# a401-diode-distortion.net
KiCad netlist of a schematic drawn in EAGLE
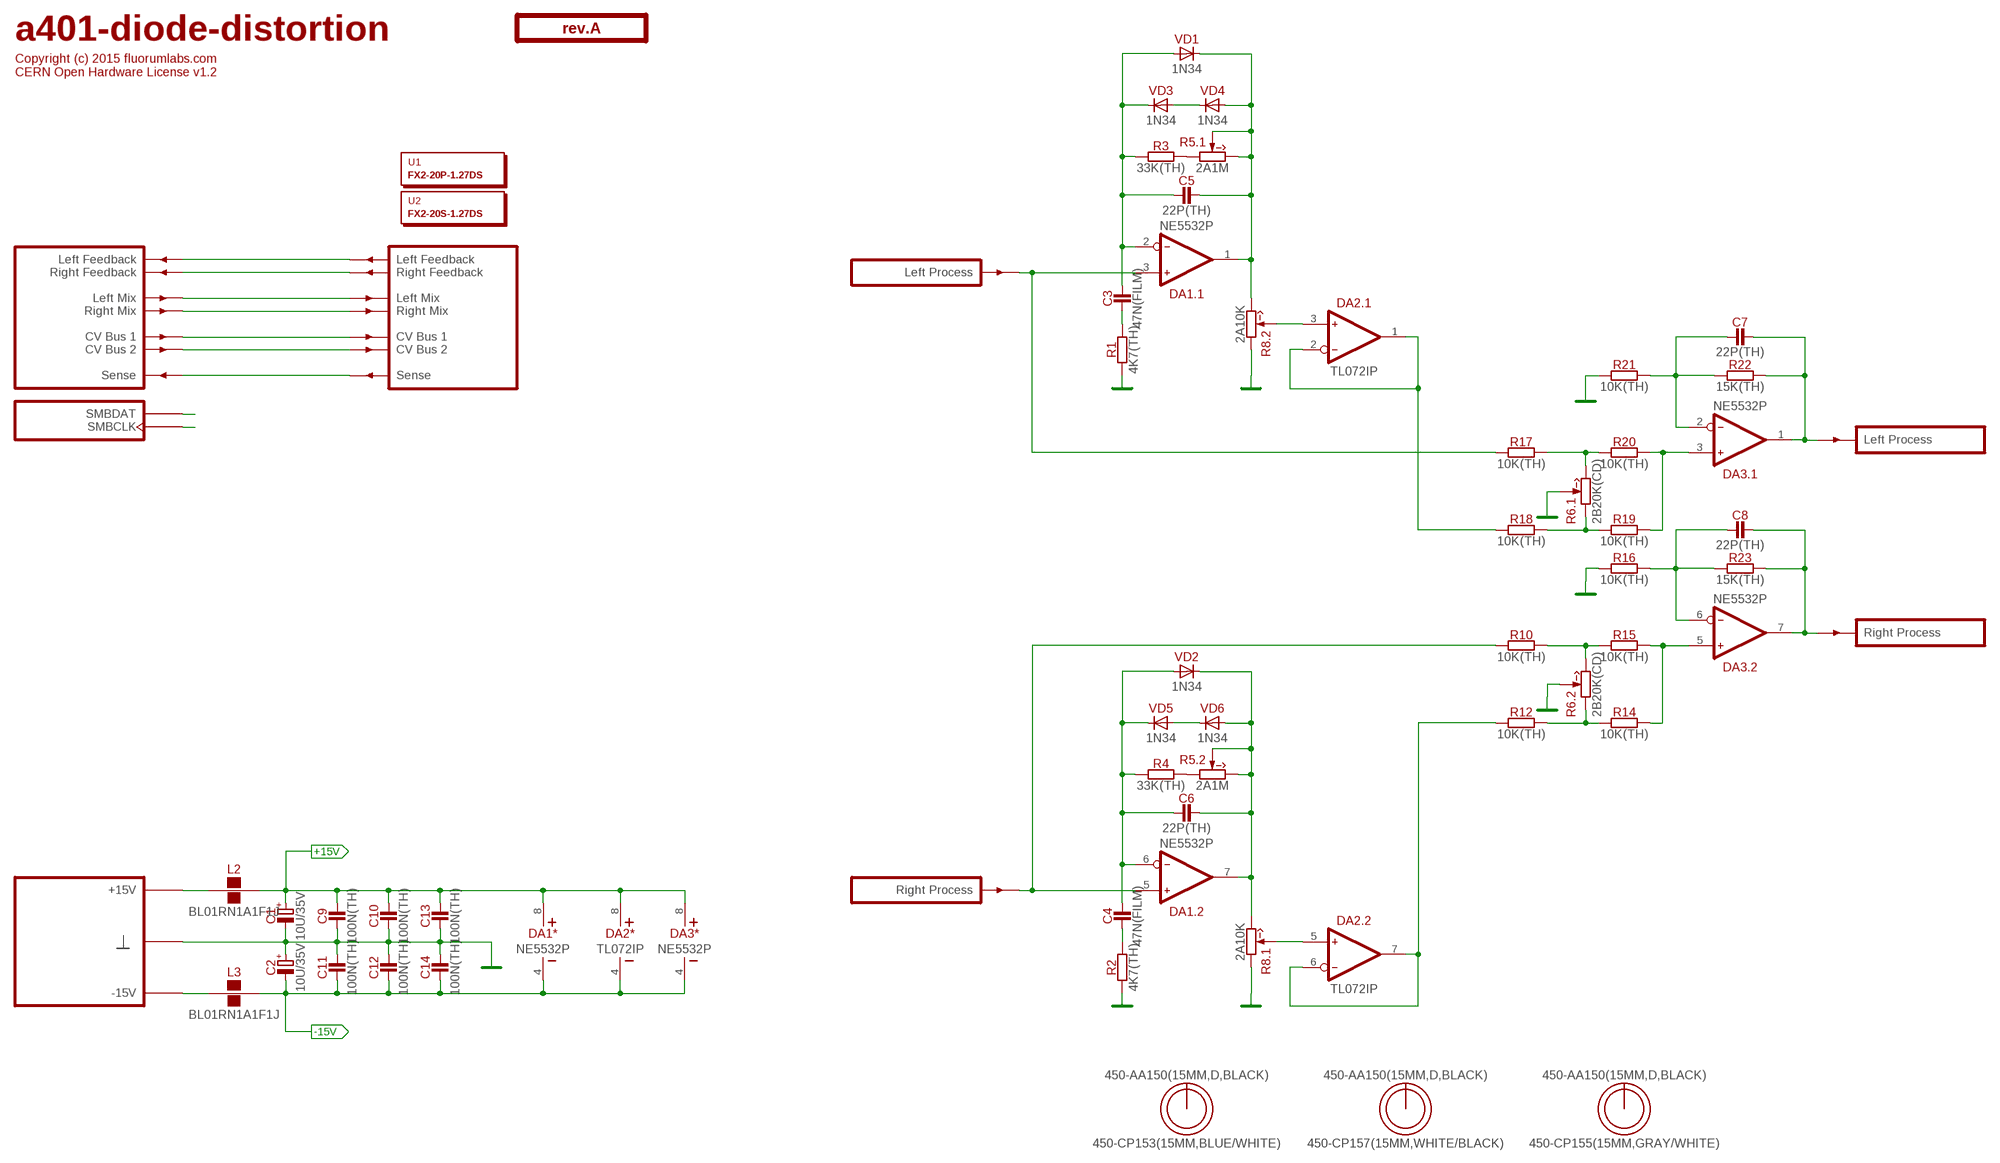
[diagram p0: schematic, sheet 1]

(export (version "E")
  (design (tool "Eeschema 10.0.6"))
  (components
    (comp (ref "C1")
      (value "10U/35V")
      (footprint "eagle-import:E2-5")
      (libsource (lib "eagle-import") (part "?10U/35V"))
    )
    (comp (ref "C2")
      (value "10U/35V")
      (footprint "eagle-import:E2-5")
      (libsource (lib "eagle-import") (part "?10U/35V"))
    )
    (comp (ref "C3")
      (value "47N(FILM)")
      (footprint "eagle-import:C050-025X075")
      (libsource (lib "eagle-import") (part "?47N(FILM)"))
    )
    (comp (ref "C4")
      (value "47N(FILM)")
      (footprint "eagle-import:C050-025X075")
      (libsource (lib "eagle-import") (part "?47N(FILM)"))
    )
    (comp (ref "C5")
      (value "22P(TH)")
      (footprint "eagle-import:C050-024X044")
      (libsource (lib "eagle-import") (part "?22P(TH)"))
    )
    (comp (ref "C6")
      (value "22P(TH)")
      (footprint "eagle-import:C050-024X044")
      (libsource (lib "eagle-import") (part "?22P(TH)"))
    )
    (comp (ref "C7")
      (value "22P(TH)")
      (footprint "eagle-import:C050-024X044")
      (libsource (lib "eagle-import") (part "?22P(TH)"))
    )
    (comp (ref "C8")
      (value "22P(TH)")
      (footprint "eagle-import:C050-024X044")
      (libsource (lib "eagle-import") (part "?22P(TH)"))
    )
    (comp (ref "C9")
      (value "100N(TH)")
      (footprint "eagle-import:C050-024X044")
      (libsource (lib "eagle-import") (part "?100N(TH)"))
    )
    (comp (ref "C10")
      (value "100N(TH)")
      (footprint "eagle-import:C050-024X044")
      (libsource (lib "eagle-import") (part "?100N(TH)"))
    )
    (comp (ref "C11")
      (value "100N(TH)")
      (footprint "eagle-import:C050-024X044")
      (libsource (lib "eagle-import") (part "?100N(TH)"))
    )
    (comp (ref "C12")
      (value "100N(TH)")
      (footprint "eagle-import:C050-024X044")
      (libsource (lib "eagle-import") (part "?100N(TH)"))
    )
    (comp (ref "C13")
      (value "100N(TH)")
      (footprint "eagle-import:C050-024X044")
      (libsource (lib "eagle-import") (part "?100N(TH)"))
    )
    (comp (ref "C14")
      (value "100N(TH)")
      (footprint "eagle-import:C050-024X044")
      (libsource (lib "eagle-import") (part "?100N(TH)"))
    )
    (comp (ref "DA1")
      (value "NE5532P")
      (footprint "eagle-import:DIP-8")
      (libsource (lib "eagle-import") (part "NE5532P"))
    )
    (comp (ref "DA2")
      (value "TL072IP")
      (footprint "eagle-import:DIP-8")
      (libsource (lib "eagle-import") (part "TL072IP"))
    )
    (comp (ref "DA3")
      (value "NE5532P")
      (footprint "eagle-import:DIP-8")
      (libsource (lib "eagle-import") (part "NE5532P"))
    )
    (comp (ref "L2")
      (value "BL01RN1A1F1J")
      (footprint "eagle-import:BL01RN1A")
      (libsource (lib "eagle-import") (part "BL01RN1A?1F1J"))
    )
    (comp (ref "L3")
      (value "BL01RN1A1F1J")
      (footprint "eagle-import:BL01RN1A")
      (libsource (lib "eagle-import") (part "BL01RN1A?1F1J"))
    )
    (comp (ref "O1")
      (value "TITLE")
      (footprint "eagle-import:EMPTY")
      (libsource (lib "eagle-import") (part "TITLE"))
    )
    (comp (ref "O2")
      (value "450-AA150(15MM,D,BLACK)")
      (footprint "eagle-import:EMPTY")
      (libsource (lib "eagle-import") (part "450-AA?150(15MM,D,BLACK)"))
    )
    (comp (ref "O3")
      (value "450-AA150(15MM,D,BLACK)")
      (footprint "eagle-import:EMPTY")
      (libsource (lib "eagle-import") (part "450-AA?150(15MM,D,BLACK)"))
    )
    (comp (ref "O4")
      (value "450-AA150(15MM,D,BLACK)")
      (footprint "eagle-import:EMPTY")
      (libsource (lib "eagle-import") (part "450-AA?150(15MM,D,BLACK)"))
    )
    (comp (ref "O5")
      (value "450-CP155(15MM,GRAY/WHITE)")
      (footprint "eagle-import:EMPTY")
      (libsource (lib "eagle-import") (part "450-C?P155(15MM,GRAY/WHITE)"))
    )
    (comp (ref "O6")
      (value "450-CP157(15MM,WHITE/BLACK)")
      (footprint "eagle-import:EMPTY")
      (libsource (lib "eagle-import") (part "450-C?P157(15MM,WHITE/BLACK)"))
    )
    (comp (ref "O7")
      (value "450-CP153(15MM,BLUE/WHITE)")
      (footprint "eagle-import:EMPTY")
      (libsource (lib "eagle-import") (part "450-C?P153(15MM,BLUE/WHITE)"))
    )
    (comp (ref "PCB1")
      (value "rev.A")
      (footprint "eagle-import:ST2-BOARD-50")
      (libsource (lib "eagle-import") (part "ST2-BOARD-50"))
    )
    (comp (ref "R1")
      (value "4K7(TH)")
      (footprint "eagle-import:R-0207_10")
      (libsource (lib "eagle-import") (part "?4K7(TH)"))
    )
    (comp (ref "R2")
      (value "4K7(TH)")
      (footprint "eagle-import:R-0207_10")
      (libsource (lib "eagle-import") (part "?4K7(TH)"))
    )
    (comp (ref "R3")
      (value "33K(TH)")
      (footprint "eagle-import:R-0207_10")
      (libsource (lib "eagle-import") (part "?33K(TH)"))
    )
    (comp (ref "R4")
      (value "33K(TH)")
      (footprint "eagle-import:R-0207_10")
      (libsource (lib "eagle-import") (part "?33K(TH)"))
    )
    (comp (ref "R5")
      (value "2A1M")
      (footprint "eagle-import:RV11-DUAL")
      (libsource (lib "eagle-import") (part "2?A1M"))
    )
    (comp (ref "R6")
      (value "2B20K(CD)")
      (footprint "eagle-import:RV11-DUAL")
      (libsource (lib "eagle-import") (part "2?B20K(CD)"))
    )
    (comp (ref "R8")
      (value "2A10K")
      (footprint "eagle-import:RV11-DUAL")
      (libsource (lib "eagle-import") (part "2?A10K"))
    )
    (comp (ref "R10")
      (value "10K(TH)")
      (footprint "eagle-import:R-0207_10")
      (libsource (lib "eagle-import") (part "?10K(TH)"))
    )
    (comp (ref "R12")
      (value "10K(TH)")
      (footprint "eagle-import:R-0207_10")
      (libsource (lib "eagle-import") (part "?10K(TH)"))
    )
    (comp (ref "R14")
      (value "10K(TH)")
      (footprint "eagle-import:R-0207_10")
      (libsource (lib "eagle-import") (part "?10K(TH)"))
    )
    (comp (ref "R15")
      (value "10K(TH)")
      (footprint "eagle-import:R-0207_10")
      (libsource (lib "eagle-import") (part "?10K(TH)"))
    )
    (comp (ref "R16")
      (value "10K(TH)")
      (footprint "eagle-import:R-0207_10")
      (libsource (lib "eagle-import") (part "?10K(TH)"))
    )
    (comp (ref "R17")
      (value "10K(TH)")
      (footprint "eagle-import:R-0207_10")
      (libsource (lib "eagle-import") (part "?10K(TH)"))
    )
    (comp (ref "R18")
      (value "10K(TH)")
      (footprint "eagle-import:R-0207_10")
      (libsource (lib "eagle-import") (part "?10K(TH)"))
    )
    (comp (ref "R19")
      (value "10K(TH)")
      (footprint "eagle-import:R-0207_10")
      (libsource (lib "eagle-import") (part "?10K(TH)"))
    )
    (comp (ref "R20")
      (value "10K(TH)")
      (footprint "eagle-import:R-0207_10")
      (libsource (lib "eagle-import") (part "?10K(TH)"))
    )
    (comp (ref "R21")
      (value "10K(TH)")
      (footprint "eagle-import:R-0207_10")
      (libsource (lib "eagle-import") (part "?10K(TH)"))
    )
    (comp (ref "R22")
      (value "15K(TH)")
      (footprint "eagle-import:R-0207_10")
      (libsource (lib "eagle-import") (part "?15K(TH)"))
    )
    (comp (ref "R23")
      (value "15K(TH)")
      (footprint "eagle-import:R-0207_10")
      (libsource (lib "eagle-import") (part "?15K(TH)"))
    )
    (comp (ref "U1")
      (value "FX2-20P-1.27DS")
      (footprint "eagle-import:EMPTY")
      (libsource (lib "eagle-import") (part "?FX2-20P-1.27DS"))
    )
    (comp (ref "U2")
      (value "FX2-20S-1.27DS")
      (footprint "eagle-import:EMPTY")
      (libsource (lib "eagle-import") (part "?FX2-20S-1.27DS"))
    )
    (comp (ref "VD1")
      (value "1N34")
      (footprint "eagle-import:DO35-15")
      (libsource (lib "eagle-import") (part "?1N34"))
    )
    (comp (ref "VD2")
      (value "1N34")
      (footprint "eagle-import:DO35-15")
      (libsource (lib "eagle-import") (part "?1N34"))
    )
    (comp (ref "VD3")
      (value "1N34")
      (footprint "eagle-import:DO35-15")
      (libsource (lib "eagle-import") (part "?1N34"))
    )
    (comp (ref "VD4")
      (value "1N34")
      (footprint "eagle-import:DO35-15")
      (libsource (lib "eagle-import") (part "?1N34"))
    )
    (comp (ref "VD5")
      (value "1N34")
      (footprint "eagle-import:DO35-15")
      (libsource (lib "eagle-import") (part "?1N34"))
    )
    (comp (ref "VD6")
      (value "1N34")
      (footprint "eagle-import:DO35-15")
      (libsource (lib "eagle-import") (part "?1N34"))
    )
  )
  (nets
    (net (code "1") (name "+15V") (class "Default")
      (node (ref "C1") (pin "+") (pinfunction "+_+") (pintype "passive"))
      (node (ref "C10") (pin "2") (pinfunction "2_2") (pintype "passive"))
      (node (ref "C13") (pin "2") (pinfunction "2_2") (pintype "passive"))
      (node (ref "C9") (pin "2") (pinfunction "2_2") (pintype "passive"))
      (node (ref "DA1") (pin "8") (pinfunction "V+_8") (pintype "power_in"))
      (node (ref "DA2") (pin "8") (pinfunction "V+_8") (pintype "power_in"))
      (node (ref "DA3") (pin "8") (pinfunction "V+_8") (pintype "power_in"))
      (node (ref "L2") (pin "2") (pinfunction "2_2") (pintype "passive"))
    )
    (net (code "2") (name "-15V") (class "Default")
      (node (ref "C11") (pin "1") (pinfunction "1_1") (pintype "passive"))
      (node (ref "C12") (pin "1") (pinfunction "1_1") (pintype "passive"))
      (node (ref "C14") (pin "1") (pinfunction "1_1") (pintype "passive"))
      (node (ref "C2") (pin "-") (pinfunction "-_-") (pintype "passive"))
      (node (ref "DA1") (pin "4") (pinfunction "V-_4") (pintype "power_in"))
      (node (ref "DA2") (pin "4") (pinfunction "V-_4") (pintype "power_in"))
      (node (ref "DA3") (pin "4") (pinfunction "V-_4") (pintype "power_in"))
      (node (ref "L3") (pin "2") (pinfunction "2_2") (pintype "passive"))
    )
    (net (code "3") (name "GND") (class "Default")
      (node (ref "C1") (pin "-") (pinfunction "-_-") (pintype "passive"))
      (node (ref "C10") (pin "1") (pinfunction "1_1") (pintype "passive"))
      (node (ref "C11") (pin "2") (pinfunction "2_2") (pintype "passive"))
      (node (ref "C12") (pin "2") (pinfunction "2_2") (pintype "passive"))
      (node (ref "C13") (pin "1") (pinfunction "1_1") (pintype "passive"))
      (node (ref "C14") (pin "2") (pinfunction "2_2") (pintype "passive"))
      (node (ref "C2") (pin "+") (pinfunction "+_+") (pintype "passive"))
      (node (ref "C9") (pin "1") (pinfunction "1_1") (pintype "passive"))
      (node (ref "PCB1") (pin "B4") (pinfunction "GND_B4") (pintype "bidirectional"))
      (node (ref "PCB1") (pin "B4'") (pinfunction "GND_B4'") (pintype "bidirectional"))
      (node (ref "PCB1") (pin "B5") (pinfunction "GND_B5") (pintype "bidirectional"))
      (node (ref "PCB1") (pin "B5'") (pinfunction "GND_B5'") (pintype "bidirectional"))
      (node (ref "PCB1") (pin "B6") (pinfunction "GND_B6") (pintype "bidirectional"))
      (node (ref "PCB1") (pin "B6'") (pinfunction "GND_B6'") (pintype "bidirectional"))
      (node (ref "PCB1") (pin "B7") (pinfunction "GND_B7") (pintype "bidirectional"))
      (node (ref "PCB1") (pin "B7'") (pinfunction "GND_B7'") (pintype "bidirectional"))
      (node (ref "PCB1") (pin "B8") (pinfunction "GND_B8") (pintype "bidirectional"))
      (node (ref "PCB1") (pin "B8'") (pinfunction "GND_B8'") (pintype "bidirectional"))
      (node (ref "R1") (pin "1") (pinfunction "1_1") (pintype "passive"))
      (node (ref "R16") (pin "1") (pinfunction "1_1") (pintype "passive"))
      (node (ref "R2") (pin "1") (pinfunction "1_1") (pintype "passive"))
      (node (ref "R21") (pin "1") (pinfunction "1_1") (pintype "passive"))
      (node (ref "R6") (pin "2") (pinfunction "W_2") (pintype "passive"))
      (node (ref "R6") (pin "2'") (pinfunction "W_2'") (pintype "passive"))
      (node (ref "R8") (pin "1") (pinfunction "CCW_1") (pintype "passive"))
      (node (ref "R8") (pin "1'") (pinfunction "CCW_1'") (pintype "passive"))
    )
    (net (code "4") (name "Net-(C3-Pad1)") (class "Default")
      (node (ref "C3") (pin "1") (pinfunction "1_1") (pintype "passive"))
      (node (ref "R1") (pin "2") (pinfunction "2_2") (pintype "passive"))
    )
    (net (code "5") (name "Net-(C4-Pad1)") (class "Default")
      (node (ref "C4") (pin "1") (pinfunction "1_1") (pintype "passive"))
      (node (ref "R2") (pin "2") (pinfunction "2_2") (pintype "passive"))
    )
    (net (code "6") (name "Net-(DA1B-IN+)") (class "Default")
      (node (ref "DA1") (pin "3") (pinfunction "IN+_3") (pintype "input"))
      (node (ref "PCB1") (pin "BINL") (pinfunction "INL_BINL") (pintype "bidirectional"))
      (node (ref "R17") (pin "1") (pinfunction "1_1") (pintype "passive"))
    )
    (net (code "7") (name "Net-(DA1B-IN-)") (class "Default")
      (node (ref "C3") (pin "2") (pinfunction "2_2") (pintype "passive"))
      (node (ref "C5") (pin "1") (pinfunction "1_1") (pintype "passive"))
      (node (ref "DA1") (pin "2") (pinfunction "IN-_2") (pintype "input"))
      (node (ref "R3") (pin "1") (pinfunction "1_1") (pintype "passive"))
      (node (ref "VD1") (pin "A") (pinfunction "A_A") (pintype "passive"))
      (node (ref "VD3") (pin "C") (pinfunction "C_C") (pintype "passive"))
    )
    (net (code "8") (name "Net-(DA1B-OUT)") (class "Default")
      (node (ref "C5") (pin "2") (pinfunction "2_2") (pintype "passive"))
      (node (ref "DA1") (pin "1") (pinfunction "OUT_1") (pintype "output"))
      (node (ref "R5") (pin "2") (pinfunction "W_2") (pintype "passive"))
      (node (ref "R5") (pin "3") (pinfunction "CW_3") (pintype "passive"))
      (node (ref "R8") (pin "3'") (pinfunction "CW_3'") (pintype "passive"))
      (node (ref "VD1") (pin "C") (pinfunction "C_C") (pintype "passive"))
      (node (ref "VD4") (pin "A") (pinfunction "A_A") (pintype "passive"))
    )
    (net (code "9") (name "Net-(DA1C-IN+)") (class "Default")
      (node (ref "DA1") (pin "5") (pinfunction "IN+_5") (pintype "input"))
      (node (ref "PCB1") (pin "BINR") (pinfunction "INR_BINR") (pintype "bidirectional"))
      (node (ref "R10") (pin "1") (pinfunction "1_1") (pintype "passive"))
    )
    (net (code "10") (name "Net-(DA1C-IN-)") (class "Default")
      (node (ref "C4") (pin "2") (pinfunction "2_2") (pintype "passive"))
      (node (ref "C6") (pin "1") (pinfunction "1_1") (pintype "passive"))
      (node (ref "DA1") (pin "6") (pinfunction "IN-_6") (pintype "input"))
      (node (ref "R4") (pin "1") (pinfunction "1_1") (pintype "passive"))
      (node (ref "VD2") (pin "A") (pinfunction "A_A") (pintype "passive"))
      (node (ref "VD5") (pin "C") (pinfunction "C_C") (pintype "passive"))
    )
    (net (code "11") (name "Net-(DA1C-OUT)") (class "Default")
      (node (ref "C6") (pin "2") (pinfunction "2_2") (pintype "passive"))
      (node (ref "DA1") (pin "7") (pinfunction "OUT_7") (pintype "output"))
      (node (ref "R5") (pin "2'") (pinfunction "W_2'") (pintype "passive"))
      (node (ref "R5") (pin "3'") (pinfunction "CW_3'") (pintype "passive"))
      (node (ref "R8") (pin "3") (pinfunction "CW_3") (pintype "passive"))
      (node (ref "VD2") (pin "C") (pinfunction "C_C") (pintype "passive"))
      (node (ref "VD6") (pin "A") (pinfunction "A_A") (pintype "passive"))
    )
    (net (code "12") (name "Net-(DA2B-IN+)") (class "Default")
      (node (ref "DA2") (pin "3") (pinfunction "IN+_3") (pintype "input"))
      (node (ref "R8") (pin "2'") (pinfunction "W_2'") (pintype "passive"))
    )
    (net (code "13") (name "Net-(DA2B-IN-)") (class "Default")
      (node (ref "DA2") (pin "1") (pinfunction "OUT_1") (pintype "output"))
      (node (ref "DA2") (pin "2") (pinfunction "IN-_2") (pintype "input"))
      (node (ref "R18") (pin "1") (pinfunction "1_1") (pintype "passive"))
    )
    (net (code "14") (name "Net-(DA2C-IN+)") (class "Default")
      (node (ref "DA2") (pin "5") (pinfunction "IN+_5") (pintype "input"))
      (node (ref "R8") (pin "2") (pinfunction "W_2") (pintype "passive"))
    )
    (net (code "15") (name "Net-(DA2C-IN-)") (class "Default")
      (node (ref "DA2") (pin "6") (pinfunction "IN-_6") (pintype "input"))
      (node (ref "DA2") (pin "7") (pinfunction "OUT_7") (pintype "output"))
      (node (ref "R12") (pin "1") (pinfunction "1_1") (pintype "passive"))
    )
    (net (code "16") (name "Net-(DA3B-IN+)") (class "Default")
      (node (ref "DA3") (pin "3") (pinfunction "IN+_3") (pintype "input"))
      (node (ref "R19") (pin "2") (pinfunction "2_2") (pintype "passive"))
      (node (ref "R20") (pin "2") (pinfunction "2_2") (pintype "passive"))
    )
    (net (code "17") (name "Net-(DA3B-IN-)") (class "Default")
      (node (ref "C7") (pin "1") (pinfunction "1_1") (pintype "passive"))
      (node (ref "DA3") (pin "2") (pinfunction "IN-_2") (pintype "input"))
      (node (ref "R21") (pin "2") (pinfunction "2_2") (pintype "passive"))
      (node (ref "R22") (pin "1") (pinfunction "1_1") (pintype "passive"))
    )
    (net (code "18") (name "Net-(DA3B-OUT)") (class "Default")
      (node (ref "C7") (pin "2") (pinfunction "2_2") (pintype "passive"))
      (node (ref "DA3") (pin "1") (pinfunction "OUT_1") (pintype "output"))
      (node (ref "PCB1") (pin "BOUTL'") (pinfunction "OUTL_BOUTL'") (pintype "bidirectional"))
      (node (ref "R22") (pin "2") (pinfunction "2_2") (pintype "passive"))
    )
    (net (code "19") (name "Net-(DA3C-IN+)") (class "Default")
      (node (ref "DA3") (pin "5") (pinfunction "IN+_5") (pintype "input"))
      (node (ref "R14") (pin "2") (pinfunction "2_2") (pintype "passive"))
      (node (ref "R15") (pin "2") (pinfunction "2_2") (pintype "passive"))
    )
    (net (code "20") (name "Net-(DA3C-IN-)") (class "Default")
      (node (ref "C8") (pin "1") (pinfunction "1_1") (pintype "passive"))
      (node (ref "DA3") (pin "6") (pinfunction "IN-_6") (pintype "input"))
      (node (ref "R16") (pin "2") (pinfunction "2_2") (pintype "passive"))
      (node (ref "R23") (pin "1") (pinfunction "1_1") (pintype "passive"))
    )
    (net (code "21") (name "Net-(DA3C-OUT)") (class "Default")
      (node (ref "C8") (pin "2") (pinfunction "2_2") (pintype "passive"))
      (node (ref "DA3") (pin "7") (pinfunction "OUT_7") (pintype "output"))
      (node (ref "PCB1") (pin "BOUTR'") (pinfunction "OUTR_BOUTR'") (pintype "bidirectional"))
      (node (ref "R23") (pin "2") (pinfunction "2_2") (pintype "passive"))
    )
    (net (code "22") (name "Net-(L2-Pad1)") (class "Default")
      (node (ref "L2") (pin "1") (pinfunction "1_1") (pintype "passive"))
      (node (ref "PCB1") (pin "A+15") (pinfunction "P+15V_A+15") (pintype "bidirectional"))
      (node (ref "PCB1") (pin "A+15'") (pinfunction "P+15V_A+15'") (pintype "bidirectional"))
      (node (ref "PCB1") (pin "B+15") (pinfunction "P+15V_B+15") (pintype "bidirectional"))
      (node (ref "PCB1") (pin "B+15'") (pinfunction "P+15V_B+15'") (pintype "bidirectional"))
    )
    (net (code "23") (name "Net-(L3-Pad1)") (class "Default")
      (node (ref "L3") (pin "1") (pinfunction "1_1") (pintype "passive"))
      (node (ref "PCB1") (pin "A-15") (pinfunction "P-15V_A-15") (pintype "bidirectional"))
      (node (ref "PCB1") (pin "A-15'") (pinfunction "P-15V_A-15'") (pintype "bidirectional"))
      (node (ref "PCB1") (pin "B-15") (pinfunction "P-15V_B-15") (pintype "bidirectional"))
      (node (ref "PCB1") (pin "B-15'") (pinfunction "P-15V_B-15'") (pintype "bidirectional"))
    )
    (net (code "24") (name "Net-(PCB1F-CV1)") (class "Default")
      (node (ref "PCB1") (pin "ACV1") (pinfunction "CV1_ACV1") (pintype "bidirectional"))
      (node (ref "PCB1") (pin "ACV1'") (pinfunction "CV1'_ACV1'") (pintype "bidirectional"))
    )
    (net (code "25") (name "Net-(PCB1F-CV2)") (class "Default")
      (node (ref "PCB1") (pin "ACV2") (pinfunction "CV2_ACV2") (pintype "bidirectional"))
      (node (ref "PCB1") (pin "ACV2'") (pinfunction "CV2'_ACV2'") (pintype "bidirectional"))
    )
    (net (code "26") (name "Net-(PCB1F-LFBK)") (class "Default")
      (node (ref "PCB1") (pin "ALFBK") (pinfunction "LFBK_ALFBK") (pintype "bidirectional"))
      (node (ref "PCB1") (pin "ALFBK'") (pinfunction "LFBK'_ALFBK'") (pintype "bidirectional"))
    )
    (net (code "27") (name "Net-(PCB1F-LMIX)") (class "Default")
      (node (ref "PCB1") (pin "ALMIX") (pinfunction "LMIX_ALMIX") (pintype "bidirectional"))
      (node (ref "PCB1") (pin "ALMIX'") (pinfunction "LMIX'_ALMIX'") (pintype "bidirectional"))
    )
    (net (code "28") (name "Net-(PCB1F-RFBK)") (class "Default")
      (node (ref "PCB1") (pin "ARFBK") (pinfunction "RFBK_ARFBK") (pintype "bidirectional"))
      (node (ref "PCB1") (pin "ARFBK'") (pinfunction "RFBK'_ARFBK'") (pintype "bidirectional"))
    )
    (net (code "29") (name "Net-(PCB1F-RMIX)") (class "Default")
      (node (ref "PCB1") (pin "ARMIX") (pinfunction "RMIX_ARMIX") (pintype "bidirectional"))
      (node (ref "PCB1") (pin "ARMIX'") (pinfunction "RMIX'_ARMIX'") (pintype "bidirectional"))
    )
    (net (code "30") (name "Net-(PCB1F-SENSE)") (class "Default")
      (node (ref "PCB1") (pin "BSENSE") (pinfunction "SENSE_BSENSE") (pintype "bidirectional"))
      (node (ref "PCB1") (pin "BSENSE'") (pinfunction "SENSE'_BSENSE'") (pintype "bidirectional"))
    )
    (net (code "31") (name "Net-(PCB1H-SMBCLK-PadASMBCLK')") (class "Default")
      (node (ref "PCB1") (pin "ASMBCLK") (pinfunction "SMBCLK_ASMBCLK") (pintype "bidirectional"))
      (node (ref "PCB1") (pin "ASMBCLK'") (pinfunction "SMBCLK_ASMBCLK'") (pintype "bidirectional"))
    )
    (net (code "32") (name "Net-(PCB1H-SMBDAT-PadASMBDAT')") (class "Default")
      (node (ref "PCB1") (pin "ASMBDAT") (pinfunction "SMBDAT_ASMBDAT") (pintype "bidirectional"))
      (node (ref "PCB1") (pin "ASMBDAT'") (pinfunction "SMBDAT_ASMBDAT'") (pintype "bidirectional"))
    )
    (net (code "33") (name "Net-(R5A-CCW)") (class "Default")
      (node (ref "R3") (pin "2") (pinfunction "2_2") (pintype "passive"))
      (node (ref "R5") (pin "1") (pinfunction "CCW_1") (pintype "passive"))
    )
    (net (code "34") (name "Net-(R5B-CCW)") (class "Default")
      (node (ref "R4") (pin "2") (pinfunction "2_2") (pintype "passive"))
      (node (ref "R5") (pin "1'") (pinfunction "CCW_1'") (pintype "passive"))
    )
    (net (code "35") (name "Net-(R6A-CCW)") (class "Default")
      (node (ref "R18") (pin "2") (pinfunction "2_2") (pintype "passive"))
      (node (ref "R19") (pin "1") (pinfunction "1_1") (pintype "passive"))
      (node (ref "R6") (pin "1") (pinfunction "CCW_1") (pintype "passive"))
    )
    (net (code "36") (name "Net-(R6A-CW)") (class "Default")
      (node (ref "R17") (pin "2") (pinfunction "2_2") (pintype "passive"))
      (node (ref "R20") (pin "1") (pinfunction "1_1") (pintype "passive"))
      (node (ref "R6") (pin "3") (pinfunction "CW_3") (pintype "passive"))
    )
    (net (code "37") (name "Net-(R6B-CCW)") (class "Default")
      (node (ref "R12") (pin "2") (pinfunction "2_2") (pintype "passive"))
      (node (ref "R14") (pin "1") (pinfunction "1_1") (pintype "passive"))
      (node (ref "R6") (pin "1'") (pinfunction "CCW_1'") (pintype "passive"))
    )
    (net (code "38") (name "Net-(R6B-CW)") (class "Default")
      (node (ref "R10") (pin "2") (pinfunction "2_2") (pintype "passive"))
      (node (ref "R15") (pin "1") (pinfunction "1_1") (pintype "passive"))
      (node (ref "R6") (pin "3'") (pinfunction "CW_3'") (pintype "passive"))
    )
    (net (code "39") (name "Net-(VD3-PadA)") (class "Default")
      (node (ref "VD3") (pin "A") (pinfunction "A_A") (pintype "passive"))
      (node (ref "VD4") (pin "C") (pinfunction "C_C") (pintype "passive"))
    )
    (net (code "40") (name "Net-(VD5-PadA)") (class "Default")
      (node (ref "VD5") (pin "A") (pinfunction "A_A") (pintype "passive"))
      (node (ref "VD6") (pin "C") (pinfunction "C_C") (pintype "passive"))
    )
  )
)
